# USB3_0_1.net
KiCad netlist of a schematic drawn in Altium Designer
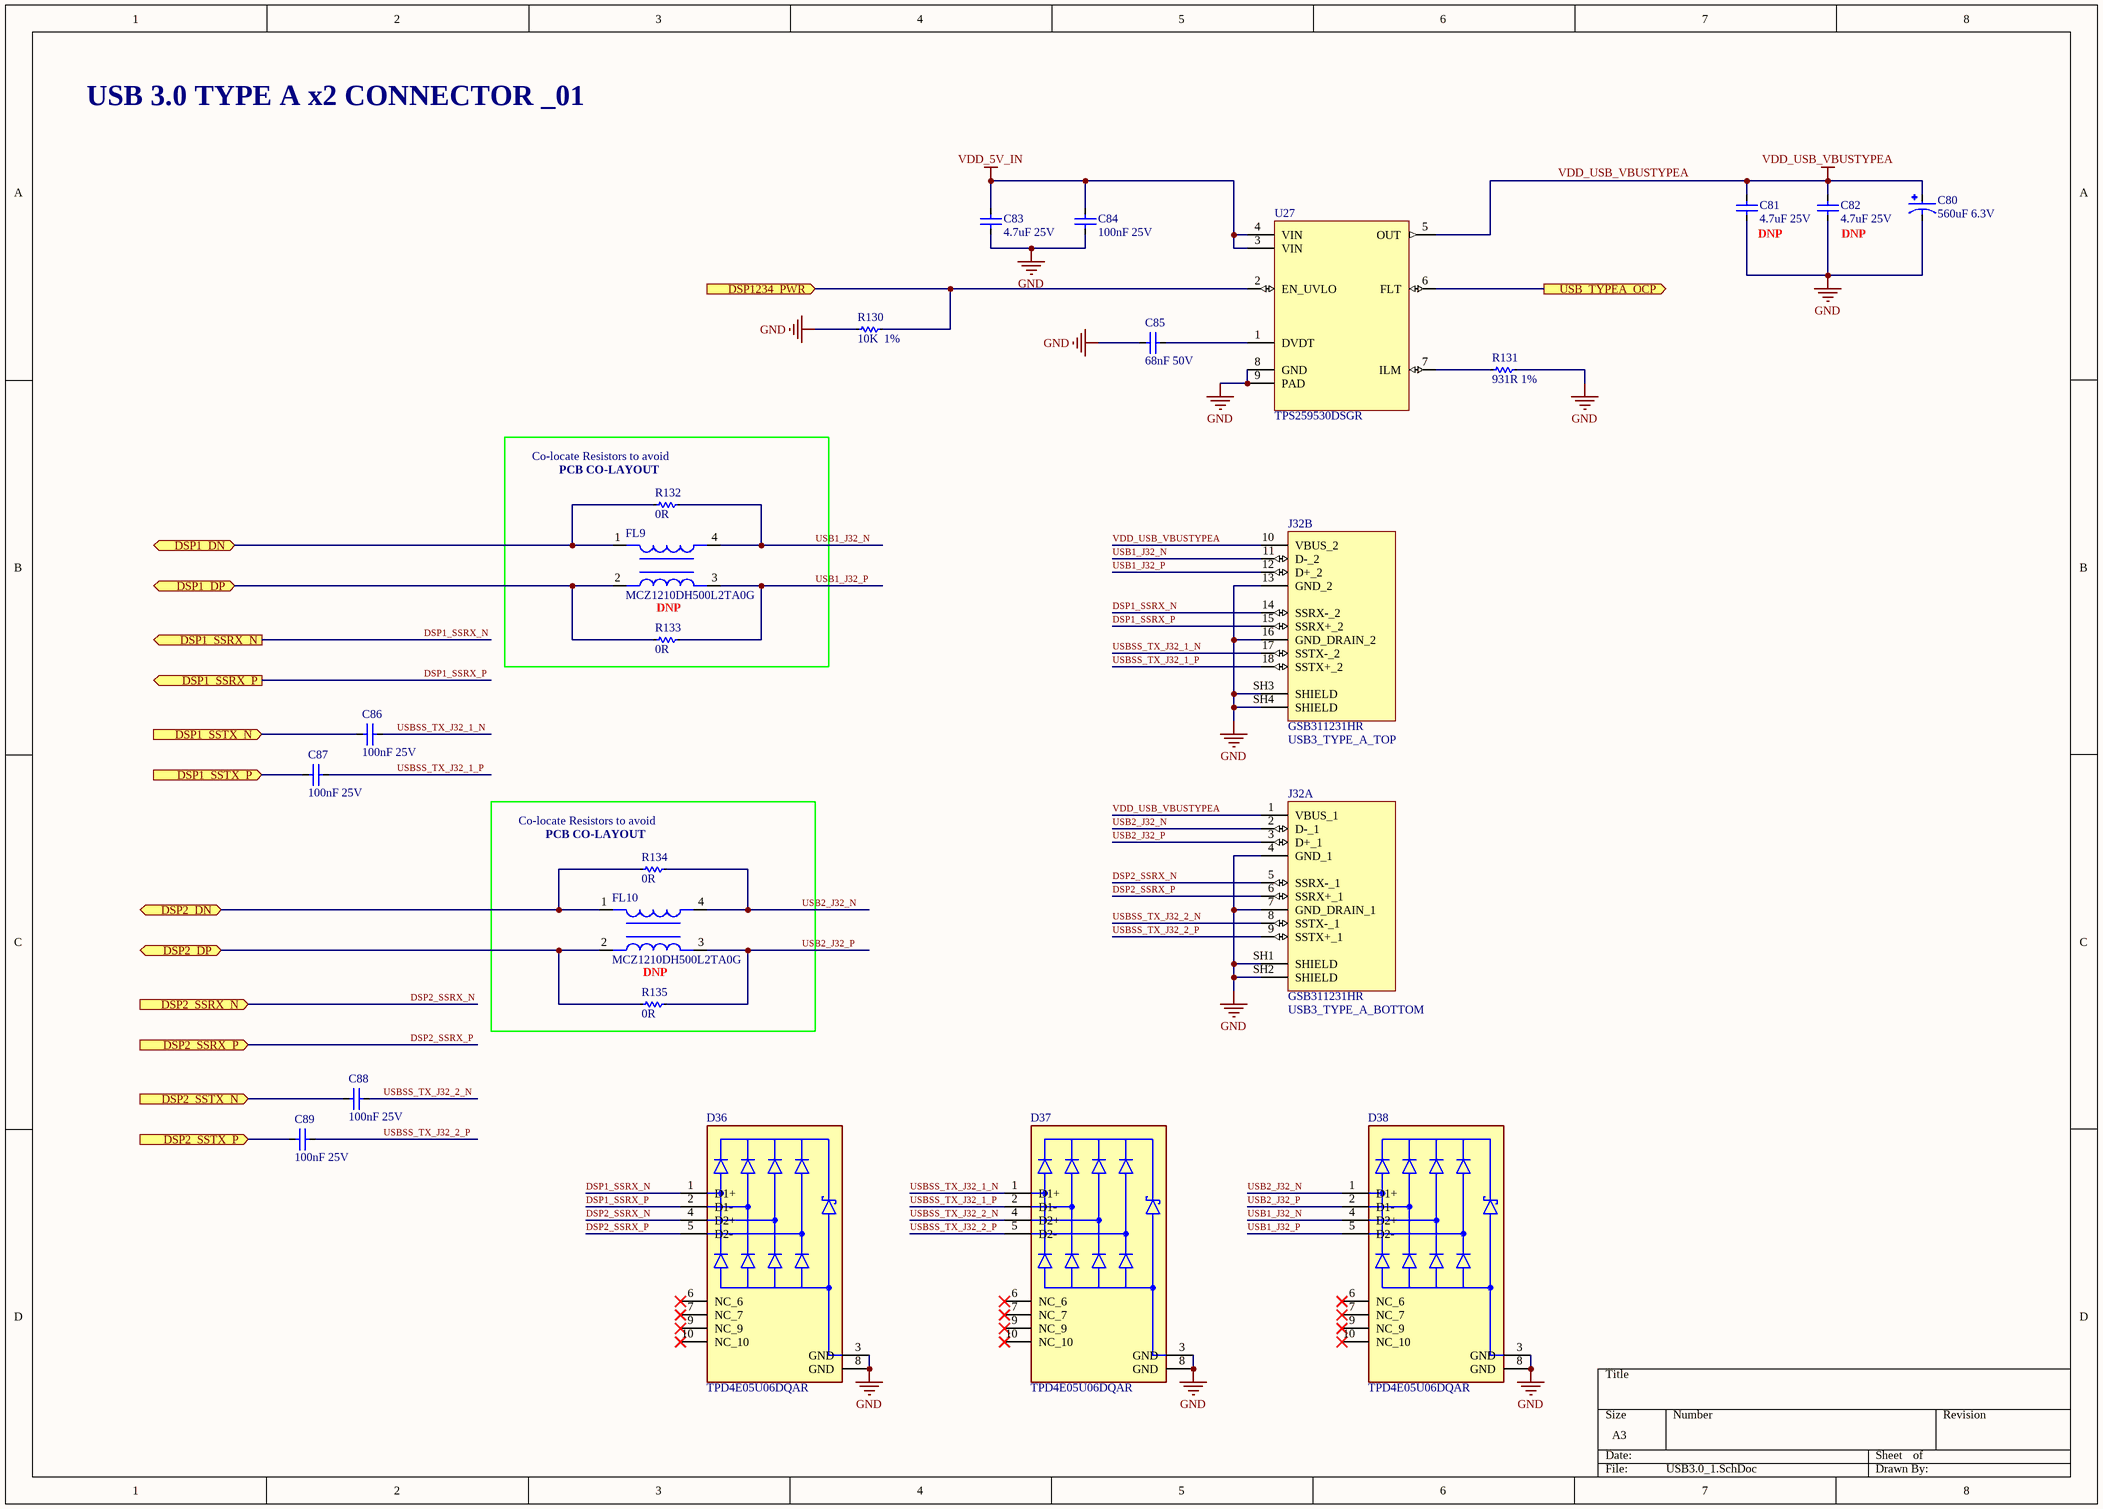
[diagram p0: USB3.0_1.SchDoc]

(export (version "E")
  (design (tool "Eeschema 10.0.6"))
  (components
    (comp (ref "C80")
      (value "560uF 6.3V")
      (footprint "CP_ELEC_8X7.7")
      (description "Cap Aluminum Polymer 560uF 6.3VDC 20% (8 X 7.7mm) SMD 0.009 Ohm 4500mA 2000h 105C T/R")
      (fields
        (field (name "MANUFACTURER") "Nichicon")
        (field (name "MANUFACTURER PART NUMBER") "RHA0J561MCN1GS")
      )
      (libsource (lib "GM_Capacitor") (part "RHA0J561MCN1GS"))
    )
    (comp (ref "C81")
      (value "4.7uF 25V")
      (footprint "C0603")
      (description "0603 4.7 uF 25 V ±10 % Tolerance X5R SMT Multilayer Ceramic Capacitor")
      (fields
        (field (name "MANUFACTURER") "Murata")
        (field (name "MANUFACTURER PART NUMBER") "GRM188R61E475KE11D")
      )
      (libsource (lib "GM_Altium_Library") (part "GRM188R61E475KE11D"))
    )
    (comp (ref "C82")
      (value "4.7uF 25V")
      (footprint "C0603")
      (description "0603 4.7 uF 25 V ±10 % Tolerance X5R SMT Multilayer Ceramic Capacitor")
      (fields
        (field (name "MANUFACTURER") "Murata")
        (field (name "MANUFACTURER PART NUMBER") "GRM188R61E475KE11D")
      )
      (libsource (lib "GM_Altium_Library") (part "GRM188R61E475KE11D"))
    )
    (comp (ref "C83")
      (value "4.7uF 25V")
      (footprint "C0603")
      (description "0603 4.7 uF 25 V ±10 % Tolerance X5R SMT Multilayer Ceramic Capacitor")
      (fields
        (field (name "MANUFACTURER") "Murata")
        (field (name "MANUFACTURER PART NUMBER") "GRM188R61E475KE11D")
      )
      (libsource (lib "GM_Altium_Library") (part "GRM188R61E475KE11D"))
    )
    (comp (ref "C84")
      (value "100nF 25V")
      (footprint "C0402")
      (description "CAP CER 0.1UF 25V X5R 0402 / High Value Multilayer Ceramic Capacitors (High dielectric type)")
      (fields
        (field (name "MANUFACTURER") "Taiyo Yuden")
        (field (name "MANUFACTURER PART NUMBER") "TMK105BJ104KV-F")
      )
      (libsource (lib "GM_Altium_Library") (part "TMK105BJ104KV-F"))
    )
    (comp (ref "C85")
      (value "68nF 50V")
      (footprint "C0805")
      (description "Cap Cer 0805 68NF 50V X7R 10%")
      (fields
        (field (name "MANUFACTURER") "KEMET")
        (field (name "MANUFACTURER PART NUMBER") "C0805C683K5RECAUTO7210")
      )
      (libsource (lib "GM_Capacitor") (part "C0805C683K5RECAUTO7210"))
    )
    (comp (ref "C86")
      (value "100nF 25V")
      (footprint "C0402")
      (description "0402 100 nF 25 V ±10 % Tolerance X7R Surface Mount Multilayer Ceramic Capacitor")
      (fields
        (field (name "MANUFACTURER") "Kyocera AVX")
        (field (name "MANUFACTURER PART NUMBER") "04023C104KAT2A")
      )
      (libsource (lib "GM_Altium_Library") (part "04023C104KAT2A"))
    )
    (comp (ref "C87")
      (value "100nF 25V")
      (footprint "C0402")
      (description "0402 100 nF 25 V ±10 % Tolerance X7R Surface Mount Multilayer Ceramic Capacitor")
      (fields
        (field (name "MANUFACTURER") "Kyocera AVX")
        (field (name "MANUFACTURER PART NUMBER") "04023C104KAT2A")
      )
      (libsource (lib "GM_Altium_Library") (part "04023C104KAT2A"))
    )
    (comp (ref "C88")
      (value "100nF 25V")
      (footprint "C0402")
      (description "0402 100 nF 25 V ±10 % Tolerance X7R Surface Mount Multilayer Ceramic Capacitor")
      (fields
        (field (name "MANUFACTURER") "Kyocera AVX")
        (field (name "MANUFACTURER PART NUMBER") "04023C104KAT2A")
      )
      (libsource (lib "GM_Altium_Library") (part "04023C104KAT2A"))
    )
    (comp (ref "C89")
      (value "100nF 25V")
      (footprint "C0402")
      (description "0402 100 nF 25 V ±10 % Tolerance X7R Surface Mount Multilayer Ceramic Capacitor")
      (fields
        (field (name "MANUFACTURER") "Kyocera AVX")
        (field (name "MANUFACTURER PART NUMBER") "04023C104KAT2A")
      )
      (libsource (lib "GM_Altium_Library") (part "04023C104KAT2A"))
    )
    (comp (ref "D36")
      (value "TPD4E05U06DQAR")
      (footprint "TPD4E05U06DQAR")
      (description "Quad 0.5-pF, 5.5-V, ±12-kV ESD protection diode for USB, HDMI & High Speed Interfaces")
      (fields (field (name "MANUFACTURER") "Texas Instruments"))
      (libsource (lib "GM_Altium_Library") (part "TPD4E05U06DQAR"))
    )
    (comp (ref "D37")
      (value "TPD4E05U06DQAR")
      (footprint "TPD4E05U06DQAR")
      (description "Quad 0.5-pF, 5.5-V, ±12-kV ESD protection diode for USB, HDMI & High Speed Interfaces")
      (fields (field (name "MANUFACTURER") "Texas Instruments"))
      (libsource (lib "GM_Altium_Library") (part "TPD4E05U06DQAR"))
    )
    (comp (ref "D38")
      (value "TPD4E05U06DQAR")
      (footprint "TPD4E05U06DQAR")
      (description "Quad 0.5-pF, 5.5-V, ±12-kV ESD protection diode for USB, HDMI & High Speed Interfaces")
      (fields (field (name "MANUFACTURER") "Texas Instruments"))
      (libsource (lib "GM_Altium_Library") (part "TPD4E05U06DQAR"))
    )
    (comp (ref "FL9")
      (value "MCZ1210DH500L2TA0G")
      (footprint "MCZ1210DH500L2TA0G")
      (description "2 Line Common Mode Choke Surface Mount 50 Ohms 100mA DCR 2.5Ohm")
      (fields (field (name "MANUFACTURER") "TDK"))
      (libsource (lib "GM_Filter") (part "MCZ1210DH500L2TA0G"))
    )
    (comp (ref "FL10")
      (value "MCZ1210DH500L2TA0G")
      (footprint "MCZ1210DH500L2TA0G")
      (description "2 Line Common Mode Choke Surface Mount 50 Ohms 100mA DCR 2.5Ohm")
      (fields (field (name "MANUFACTURER") "TDK"))
      (libsource (lib "GM_Filter") (part "MCZ1210DH500L2TA0G"))
    )
    (comp (ref "J32")
      (value "GSB311231HR")
      (footprint "GSB311231HR")
      (description "18 Position USB TYPE-A Panel Mount Through Hole Right Angle Receptacle Connector")
      (fields (field (name "MANUFACTURER") "Amphenol Communications Solutions"))
      (libsource (lib "GM_Connector") (part "GSB311231HR"))
    )
    (comp (ref "R130")
      (value "10K  1%")
      (footprint "R0402")
      (description "Res General Purpose Thick Film 0402 10K Ohm 1% 1/16W ±100ppm/°C Molded SMD Paper T/R")
      (fields
        (field (name "MANUFACTURER") "Yageo")
        (field (name "MANUFACTURER PART NUMBER") "RC0402FR-0710KP")
      )
      (libsource (lib "GM_Altium_Library") (part "RC0402FR-0710KP"))
    )
    (comp (ref "R131")
      (value "931R 1%")
      (footprint "R0402")
      (description "Res Thick Film 0402 931 Ohm 1% 1/16W ±100ppm/°C Molded SMD Paper T/R")
      (fields
        (field (name "MANUFACTURER") "Yageo")
        (field (name "MANUFACTURER PART NUMBER") "RC0402FR-07931RL")
      )
      (libsource (lib "GM_Resistor") (part "RC0402FR-07931RL"))
    )
    (comp (ref "R132")
      (value "0R")
      (footprint "R0402")
      (description "Res Jumper Thick Film 0402 0 Ohm 5% 1/16W Molded SMD Paper T/R")
      (fields
        (field (name "MANUFACTURER") "Yageo")
        (field (name "MANUFACTURER PART NUMBER") "RC0402JR-070RP")
      )
      (libsource (lib "GM_Altium_Library") (part "RC0402JR-070RP"))
    )
    (comp (ref "R133")
      (value "0R")
      (footprint "R0402")
      (description "Res Jumper Thick Film 0402 0 Ohm 5% 1/16W Molded SMD Paper T/R")
      (fields
        (field (name "MANUFACTURER") "Yageo")
        (field (name "MANUFACTURER PART NUMBER") "RC0402JR-070RP")
      )
      (libsource (lib "GM_Altium_Library") (part "RC0402JR-070RP"))
    )
    (comp (ref "R134")
      (value "0R")
      (footprint "R0402")
      (description "Res Jumper Thick Film 0402 0 Ohm 5% 1/16W Molded SMD Paper T/R")
      (fields
        (field (name "MANUFACTURER") "Yageo")
        (field (name "MANUFACTURER PART NUMBER") "RC0402JR-070RP")
      )
      (libsource (lib "GM_Altium_Library") (part "RC0402JR-070RP"))
    )
    (comp (ref "R135")
      (value "0R")
      (footprint "R0402")
      (description "Res Jumper Thick Film 0402 0 Ohm 5% 1/16W Molded SMD Paper T/R")
      (fields
        (field (name "MANUFACTURER") "Yageo")
        (field (name "MANUFACTURER PART NUMBER") "RC0402JR-070RP")
      )
      (libsource (lib "GM_Altium_Library") (part "RC0402JR-070RP"))
    )
    (comp (ref "U27")
      (value "TPS259530DSGR")
      (footprint "WSON(2X2)-8")
      (description "TPS259530 12V eFuse with Fast Overvoltage Protection 2.7V to 18V 4A 34m Ohm 8-Pin WSON T/R")
      (fields (field (name "MANUFACTURER") "Texas Instruments"))
      (libsource (lib "GM_PMIC_Drivers") (part "TPS259530DSGR"))
    )
  )
  (nets
    (net (code "1") (name "/DSP1_DN") (class "Default")
      (node (ref "FL9") (pin "1") (pinfunction "1_1") (pintype "passive"))
      (node (ref "R132") (pin "1") (pinfunction "1_1") (pintype "passive"))
    )
    (net (code "2") (name "/DSP1_DP") (class "Default")
      (node (ref "FL9") (pin "2") (pinfunction "2_2") (pintype "passive"))
      (node (ref "R133") (pin "1") (pinfunction "1_1") (pintype "passive"))
    )
    (net (code "3") (name "/DSP1_SSRX_N") (class "Default")
      (node (ref "D36") (pin "1") (pinfunction "D1+_1") (pintype "passive"))
      (node (ref "J32") (pin "14") (pinfunction "SSRX-_2_14") (pintype "bidirectional"))
    )
    (net (code "4") (name "/DSP1_SSRX_P") (class "Default")
      (node (ref "D36") (pin "2") (pinfunction "D1-_2") (pintype "passive"))
      (node (ref "J32") (pin "15") (pinfunction "SSRX+_2_15") (pintype "bidirectional"))
    )
    (net (code "5") (name "/DSP1_SSTX_N") (class "Default")
      (node (ref "C86") (pin "1") (pinfunction "1_1") (pintype "passive"))
    )
    (net (code "6") (name "/DSP1_SSTX_P") (class "Default")
      (node (ref "C87") (pin "1") (pinfunction "1_1") (pintype "passive"))
    )
    (net (code "7") (name "/DSP2_DN") (class "Default")
      (node (ref "FL10") (pin "1") (pinfunction "1_1") (pintype "passive"))
      (node (ref "R134") (pin "1") (pinfunction "1_1") (pintype "passive"))
    )
    (net (code "8") (name "/DSP2_DP") (class "Default")
      (node (ref "FL10") (pin "2") (pinfunction "2_2") (pintype "passive"))
      (node (ref "R135") (pin "1") (pinfunction "1_1") (pintype "passive"))
    )
    (net (code "9") (name "/DSP2_SSRX_N") (class "Default")
      (node (ref "D36") (pin "4") (pinfunction "D2+_4") (pintype "passive"))
      (node (ref "J32") (pin "5") (pinfunction "SSRX-_1_5") (pintype "bidirectional"))
    )
    (net (code "10") (name "/DSP2_SSRX_P") (class "Default")
      (node (ref "D36") (pin "5") (pinfunction "D2-_5") (pintype "passive"))
      (node (ref "J32") (pin "6") (pinfunction "SSRX+_1_6") (pintype "bidirectional"))
    )
    (net (code "11") (name "/DSP2_SSTX_N") (class "Default")
      (node (ref "C88") (pin "1") (pinfunction "1_1") (pintype "passive"))
    )
    (net (code "12") (name "/DSP2_SSTX_P") (class "Default")
      (node (ref "C89") (pin "1") (pinfunction "1_1") (pintype "passive"))
    )
    (net (code "13") (name "/DSP1234_PWR") (class "Default")
      (node (ref "R130") (pin "2") (pinfunction "2_2") (pintype "passive"))
      (node (ref "U27") (pin "2") (pinfunction "EN_UVLO_2") (pintype "bidirectional"))
    )
    (net (code "14") (name "/USB1_J32_N") (class "Default")
      (node (ref "D38") (pin "4") (pinfunction "D2+_4") (pintype "passive"))
      (node (ref "FL9") (pin "4") (pinfunction "4_4") (pintype "passive"))
      (node (ref "J32") (pin "11") (pinfunction "D-_2_11") (pintype "bidirectional"))
      (node (ref "R132") (pin "2") (pinfunction "2_2") (pintype "passive"))
    )
    (net (code "15") (name "/USB1_J32_P") (class "Default")
      (node (ref "D38") (pin "5") (pinfunction "D2-_5") (pintype "passive"))
      (node (ref "FL9") (pin "3") (pinfunction "3_3") (pintype "passive"))
      (node (ref "J32") (pin "12") (pinfunction "D+_2_12") (pintype "bidirectional"))
      (node (ref "R133") (pin "2") (pinfunction "2_2") (pintype "passive"))
    )
    (net (code "16") (name "/USB2_J32_N") (class "Default")
      (node (ref "D38") (pin "1") (pinfunction "D1+_1") (pintype "passive"))
      (node (ref "FL10") (pin "4") (pinfunction "4_4") (pintype "passive"))
      (node (ref "J32") (pin "2") (pinfunction "D-_1_2") (pintype "bidirectional"))
      (node (ref "R134") (pin "2") (pinfunction "2_2") (pintype "passive"))
    )
    (net (code "17") (name "/USB2_J32_P") (class "Default")
      (node (ref "D38") (pin "2") (pinfunction "D1-_2") (pintype "passive"))
      (node (ref "FL10") (pin "3") (pinfunction "3_3") (pintype "passive"))
      (node (ref "J32") (pin "3") (pinfunction "D+_1_3") (pintype "bidirectional"))
      (node (ref "R135") (pin "2") (pinfunction "2_2") (pintype "passive"))
    )
    (net (code "18") (name "/USBSS_TX_J32_1_N") (class "Default")
      (node (ref "C86") (pin "2") (pinfunction "2_2") (pintype "passive"))
      (node (ref "D37") (pin "1") (pinfunction "D1+_1") (pintype "passive"))
      (node (ref "J32") (pin "17") (pinfunction "SSTX-_2_17") (pintype "bidirectional"))
    )
    (net (code "19") (name "/USBSS_TX_J32_1_P") (class "Default")
      (node (ref "C87") (pin "2") (pinfunction "2_2") (pintype "passive"))
      (node (ref "D37") (pin "2") (pinfunction "D1-_2") (pintype "passive"))
      (node (ref "J32") (pin "18") (pinfunction "SSTX+_2_18") (pintype "bidirectional"))
    )
    (net (code "20") (name "/USBSS_TX_J32_2_N") (class "Default")
      (node (ref "C88") (pin "2") (pinfunction "2_2") (pintype "passive"))
      (node (ref "D37") (pin "4") (pinfunction "D2+_4") (pintype "passive"))
      (node (ref "J32") (pin "8") (pinfunction "SSTX-_1_8") (pintype "bidirectional"))
    )
    (net (code "21") (name "/USBSS_TX_J32_2_P") (class "Default")
      (node (ref "C89") (pin "2") (pinfunction "2_2") (pintype "passive"))
      (node (ref "D37") (pin "5") (pinfunction "D2-_5") (pintype "passive"))
      (node (ref "J32") (pin "9") (pinfunction "SSTX+_1_9") (pintype "bidirectional"))
    )
    (net (code "22") (name "/USB_TYPEA_OCP") (class "Default")
      (node (ref "U27") (pin "6") (pinfunction "FLT_6") (pintype "bidirectional"))
    )
    (net (code "23") (name "GND") (class "Default")
      (node (ref "C80") (pin "2") (pinfunction "C_2") (pintype "passive"))
      (node (ref "C81") (pin "1") (pinfunction "1_1") (pintype "passive"))
      (node (ref "C82") (pin "1") (pinfunction "1_1") (pintype "passive"))
      (node (ref "C83") (pin "1") (pinfunction "1_1") (pintype "passive"))
      (node (ref "C84") (pin "1") (pinfunction "1_1") (pintype "passive"))
      (node (ref "C85") (pin "1") (pinfunction "1_1") (pintype "passive"))
      (node (ref "D36") (pin "3") (pinfunction "GND_3") (pintype "power_in"))
      (node (ref "D36") (pin "8") (pinfunction "GND_8") (pintype "power_in"))
      (node (ref "D37") (pin "3") (pinfunction "GND_3") (pintype "power_in"))
      (node (ref "D37") (pin "8") (pinfunction "GND_8") (pintype "power_in"))
      (node (ref "D38") (pin "3") (pinfunction "GND_3") (pintype "power_in"))
      (node (ref "D38") (pin "8") (pinfunction "GND_8") (pintype "power_in"))
      (node (ref "J32") (pin "13") (pinfunction "GND_2_13") (pintype "power_in"))
      (node (ref "J32") (pin "16") (pinfunction "GND_DRAIN_2_16") (pintype "power_in"))
      (node (ref "J32") (pin "4") (pinfunction "GND_1_4") (pintype "power_in"))
      (node (ref "J32") (pin "7") (pinfunction "GND_DRAIN_1_7") (pintype "power_in"))
      (node (ref "J32") (pin "SH1") (pinfunction "SHIELD_SH1") (pintype "passive"))
      (node (ref "J32") (pin "SH2") (pinfunction "SHIELD_SH2") (pintype "passive"))
      (node (ref "J32") (pin "SH3") (pinfunction "SHIELD_SH3") (pintype "passive"))
      (node (ref "J32") (pin "SH4") (pinfunction "SHIELD_SH4") (pintype "passive"))
      (node (ref "R130") (pin "1") (pinfunction "1_1") (pintype "passive"))
      (node (ref "R131") (pin "2") (pinfunction "2_2") (pintype "passive"))
      (node (ref "U27") (pin "8") (pinfunction "GND_8") (pintype "power_in"))
      (node (ref "U27") (pin "9") (pinfunction "PAD_9") (pintype "power_in"))
    )
    (net (code "24") (name "Net-(U27-DVDT)") (class "Default")
      (node (ref "C85") (pin "2") (pinfunction "2_2") (pintype "passive"))
      (node (ref "U27") (pin "1") (pinfunction "DVDT_1") (pintype "passive"))
    )
    (net (code "25") (name "Net-(U27-ILM)") (class "Default")
      (node (ref "R131") (pin "1") (pinfunction "1_1") (pintype "passive"))
      (node (ref "U27") (pin "7") (pinfunction "ILM_7") (pintype "bidirectional"))
    )
    (net (code "26") (name "VDD_5V_IN") (class "Default")
      (node (ref "C83") (pin "2") (pinfunction "2_2") (pintype "passive"))
      (node (ref "C84") (pin "2") (pinfunction "2_2") (pintype "passive"))
      (node (ref "U27") (pin "3") (pinfunction "VIN_3") (pintype "power_in"))
      (node (ref "U27") (pin "4") (pinfunction "VIN_4") (pintype "power_in"))
    )
    (net (code "27") (name "VDD_USB_VBUSTYPEA") (class "Default")
      (node (ref "C80") (pin "1") (pinfunction "A_1") (pintype "passive"))
      (node (ref "C81") (pin "2") (pinfunction "2_2") (pintype "passive"))
      (node (ref "C82") (pin "2") (pinfunction "2_2") (pintype "passive"))
      (node (ref "J32") (pin "1") (pinfunction "VBUS_1_1") (pintype "power_in"))
      (node (ref "J32") (pin "10") (pinfunction "VBUS_2_10") (pintype "power_in"))
      (node (ref "U27") (pin "5") (pinfunction "OUT_5") (pintype "output"))
    )
    (net (code "28") (name "unconnected-(D36-NC_6-Pad6)") (class "Default")
      (node (ref "D36") (pin "6") (pinfunction "NC_6_6") (pintype "passive+no_connect"))
    )
    (net (code "29") (name "unconnected-(D36-NC_7-Pad7)") (class "Default")
      (node (ref "D36") (pin "7") (pinfunction "NC_7_7") (pintype "passive+no_connect"))
    )
    (net (code "30") (name "unconnected-(D36-NC_9-Pad9)") (class "Default")
      (node (ref "D36") (pin "9") (pinfunction "NC_9_9") (pintype "passive+no_connect"))
    )
    (net (code "31") (name "unconnected-(D36-NC_10-Pad10)") (class "Default")
      (node (ref "D36") (pin "10") (pinfunction "NC_10_10") (pintype "passive+no_connect"))
    )
    (net (code "32") (name "unconnected-(D37-NC_6-Pad6)") (class "Default")
      (node (ref "D37") (pin "6") (pinfunction "NC_6_6") (pintype "passive+no_connect"))
    )
    (net (code "33") (name "unconnected-(D37-NC_7-Pad7)") (class "Default")
      (node (ref "D37") (pin "7") (pinfunction "NC_7_7") (pintype "passive+no_connect"))
    )
    (net (code "34") (name "unconnected-(D37-NC_9-Pad9)") (class "Default")
      (node (ref "D37") (pin "9") (pinfunction "NC_9_9") (pintype "passive+no_connect"))
    )
    (net (code "35") (name "unconnected-(D37-NC_10-Pad10)") (class "Default")
      (node (ref "D37") (pin "10") (pinfunction "NC_10_10") (pintype "passive+no_connect"))
    )
    (net (code "36") (name "unconnected-(D38-NC_6-Pad6)") (class "Default")
      (node (ref "D38") (pin "6") (pinfunction "NC_6_6") (pintype "passive+no_connect"))
    )
    (net (code "37") (name "unconnected-(D38-NC_7-Pad7)") (class "Default")
      (node (ref "D38") (pin "7") (pinfunction "NC_7_7") (pintype "passive+no_connect"))
    )
    (net (code "38") (name "unconnected-(D38-NC_9-Pad9)") (class "Default")
      (node (ref "D38") (pin "9") (pinfunction "NC_9_9") (pintype "passive+no_connect"))
    )
    (net (code "39") (name "unconnected-(D38-NC_10-Pad10)") (class "Default")
      (node (ref "D38") (pin "10") (pinfunction "NC_10_10") (pintype "passive+no_connect"))
    )
  )
)
